# Adafruit_1_54in_eInk_Breakout.net
KiCad netlist of a schematic drawn in EAGLE
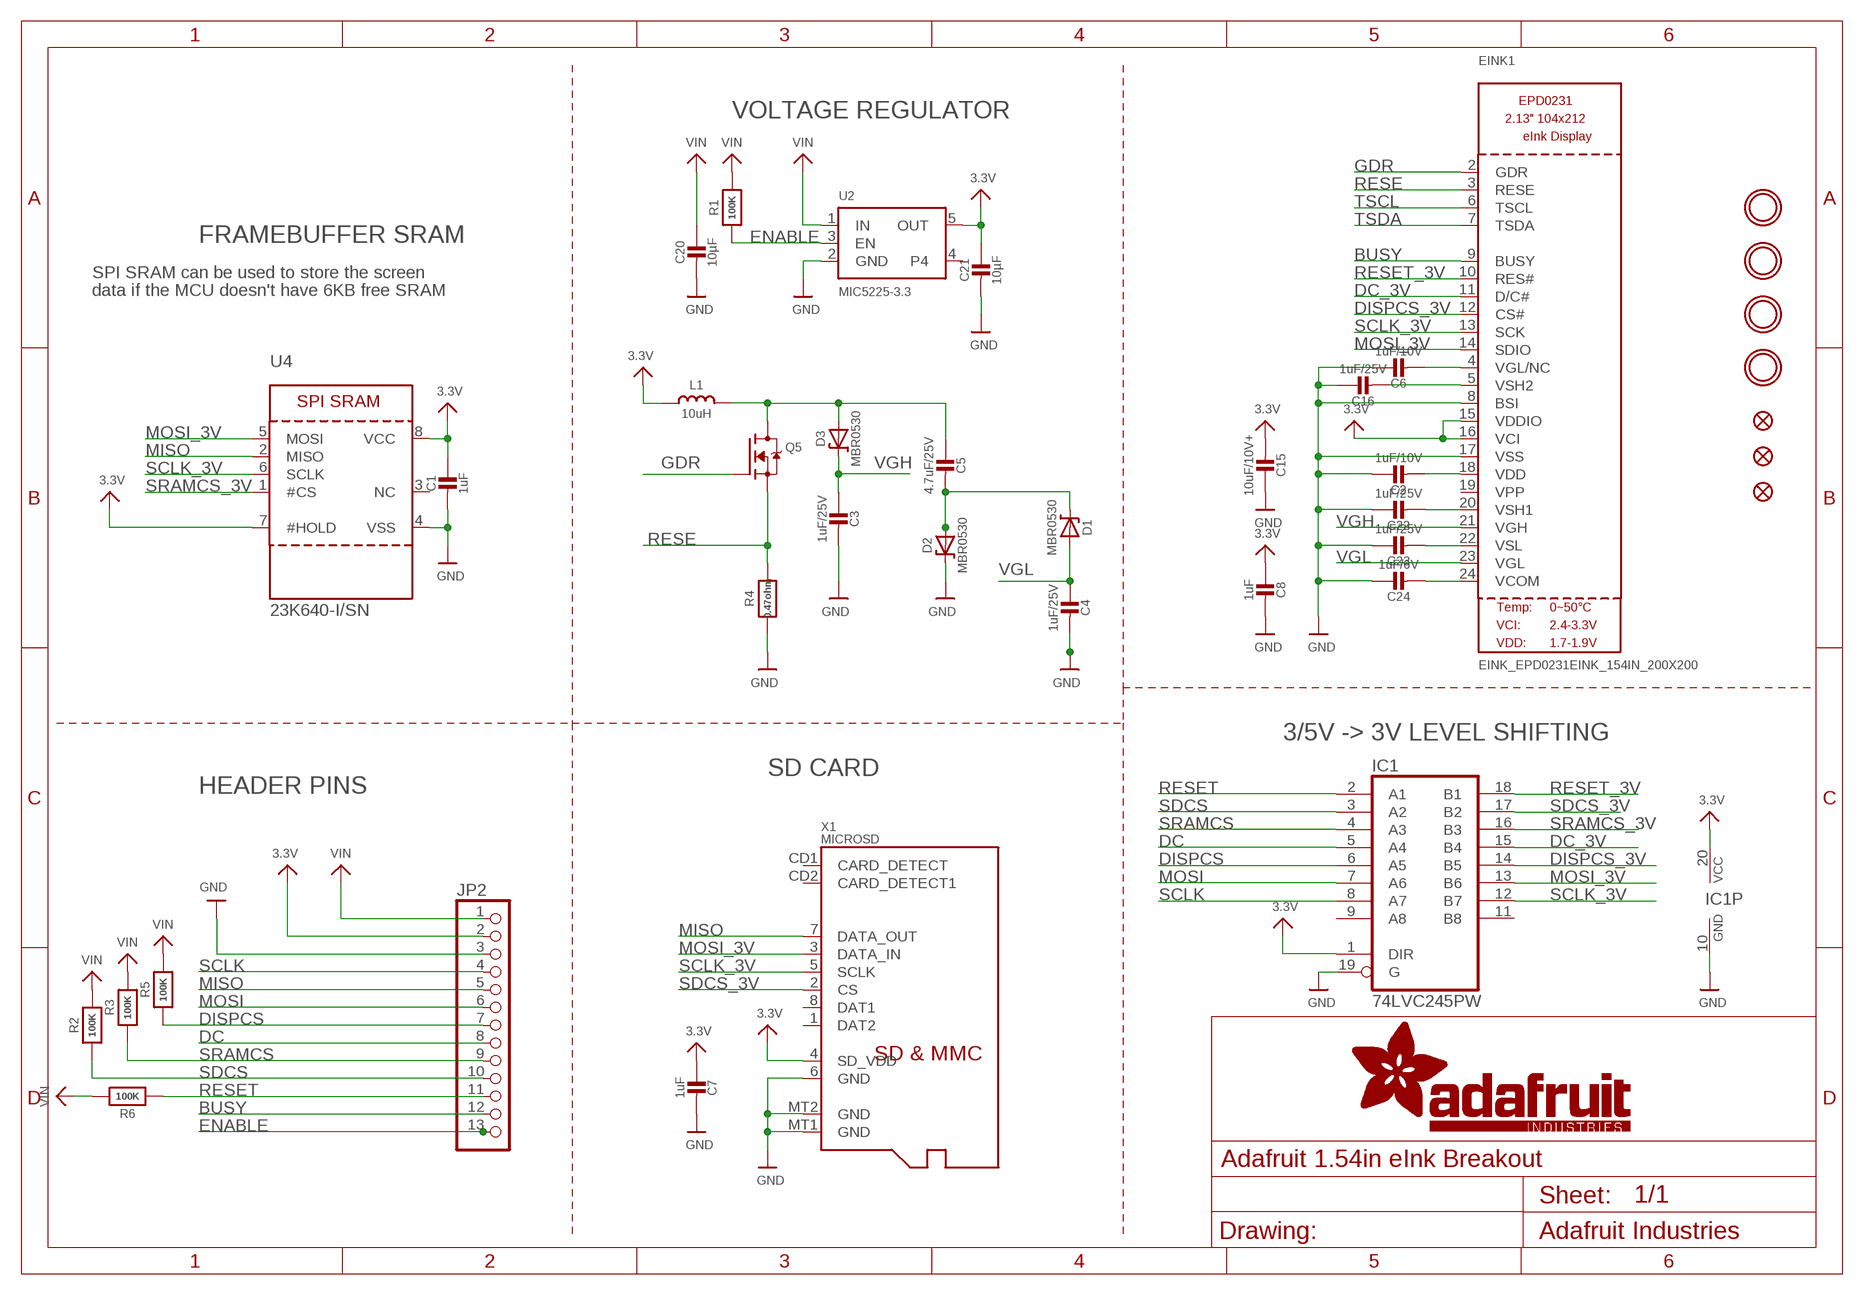
[diagram p0: schematic, sheet 1]

(export (version "E")
  (design (tool "Eeschema 10.0.6"))
  (components
    (comp (ref "C1")
      (value "1uF")
      (footprint "eagle-import:0805_10MGAP")
      (libsource (lib "eagle-import") (part "CAP_CERAMIC0805_10MGAP"))
    )
    (comp (ref "C2")
      (value "1uF/10V")
      (footprint "eagle-import:0805-NO")
      (libsource (lib "eagle-import") (part "CAP_CERAMIC0805-NOOUTLINE"))
    )
    (comp (ref "C3")
      (value "1uF/25V")
      (footprint "eagle-import:0805-NO")
      (libsource (lib "eagle-import") (part "CAP_CERAMIC0805-NOOUTLINE"))
    )
    (comp (ref "C4")
      (value "1uF/25V")
      (footprint "eagle-import:0805-NO")
      (libsource (lib "eagle-import") (part "CAP_CERAMIC0805-NOOUTLINE"))
    )
    (comp (ref "C5")
      (value "4.7uF/25V")
      (footprint "eagle-import:0805-NO")
      (libsource (lib "eagle-import") (part "CAP_CERAMIC0805-NOOUTLINE"))
    )
    (comp (ref "C6")
      (value "1uF/10V")
      (footprint "eagle-import:0805-NO")
      (libsource (lib "eagle-import") (part "CAP_CERAMIC0805-NOOUTLINE"))
    )
    (comp (ref "C7")
      (value "1uF")
      (footprint "eagle-import:0805-NO")
      (libsource (lib "eagle-import") (part "CAP_CERAMIC0805-NOOUTLINE"))
    )
    (comp (ref "C8")
      (value "1uF")
      (footprint "eagle-import:0805-NO")
      (libsource (lib "eagle-import") (part "CAP_CERAMIC0805-NOOUTLINE"))
    )
    (comp (ref "C15")
      (value "10uF/10V+")
      (footprint "eagle-import:0805-NO")
      (libsource (lib "eagle-import") (part "CAP_CERAMIC0805-NOOUTLINE"))
    )
    (comp (ref "C16")
      (value "1uF/25V")
      (footprint "eagle-import:0805-NO")
      (libsource (lib "eagle-import") (part "CAP_CERAMIC0805-NOOUTLINE"))
    )
    (comp (ref "C20")
      (value "10µF")
      (footprint "eagle-import:0805-NO")
      (libsource (lib "eagle-import") (part "CAP_CERAMIC0805-NOOUTLINE"))
    )
    (comp (ref "C21")
      (value "10µF")
      (footprint "eagle-import:0805-NO")
      (libsource (lib "eagle-import") (part "CAP_CERAMIC0805-NOOUTLINE"))
    )
    (comp (ref "C22")
      (value "1uF/25V")
      (footprint "eagle-import:0805-NO")
      (libsource (lib "eagle-import") (part "CAP_CERAMIC0805-NOOUTLINE"))
    )
    (comp (ref "C23")
      (value "1uF/25V")
      (footprint "eagle-import:0805-NO")
      (libsource (lib "eagle-import") (part "CAP_CERAMIC0805-NOOUTLINE"))
    )
    (comp (ref "C24")
      (value "1uF/6V")
      (footprint "eagle-import:0805-NO")
      (libsource (lib "eagle-import") (part "CAP_CERAMIC0805-NOOUTLINE"))
    )
    (comp (ref "D1")
      (value "MBR0530")
      (footprint "eagle-import:SOD-123")
      (libsource (lib "eagle-import") (part "DIODE-SCHOTTKYSOD-123"))
    )
    (comp (ref "D2")
      (value "MBR0530")
      (footprint "eagle-import:SOD-123")
      (libsource (lib "eagle-import") (part "DIODE-SCHOTTKYSOD-123"))
    )
    (comp (ref "D3")
      (value "MBR0530")
      (footprint "eagle-import:SOD-123")
      (libsource (lib "eagle-import") (part "DIODE-SCHOTTKYSOD-123"))
    )
    (comp (ref "EINK1")
      (value "EINK_EPD0231EINK_154IN_200X200")
      (footprint "eagle-import:EINK_154IN")
      (libsource (lib "eagle-import") (part "EINK_EPD0231EINK_154IN_200X200"))
    )
    (comp (ref "FID1")
      (value "FIDUCIAL_1MM")
      (footprint "eagle-import:FIDUCIAL_1MM")
      (libsource (lib "eagle-import") (part "FIDUCIAL_1MM"))
    )
    (comp (ref "FID2")
      (value "FIDUCIAL_1MM")
      (footprint "eagle-import:FIDUCIAL_1MM")
      (libsource (lib "eagle-import") (part "FIDUCIAL_1MM"))
    )
    (comp (ref "FID3")
      (value "FIDUCIAL_1MM")
      (footprint "eagle-import:FIDUCIAL_1MM")
      (libsource (lib "eagle-import") (part "FIDUCIAL_1MM"))
    )
    (comp (ref "IC1")
      (value "74LVC245PW")
      (footprint "eagle-import:TSSOP20")
      (libsource (lib "eagle-import") (part "74245TSSOP20"))
    )
    (comp (ref "JP2")
      (value "HEADER-1X13")
      (footprint "eagle-import:1X13_ROUND_70")
      (libsource (lib "eagle-import") (part "HEADER-1X13"))
    )
    (comp (ref "L1")
      (value "10uH")
      (footprint "eagle-import:INDUCTOR_4X4MM_NR401")
      (libsource (lib "eagle-import") (part "INDUCTORNR401"))
    )
    (comp (ref "Q5")
      (value "IRLML0100")
      (footprint "eagle-import:SOT23-3")
      (libsource (lib "eagle-import") (part "IRLML2060TRPBF"))
    )
    (comp (ref "R1")
      (value "100K")
      (footprint "eagle-import:0805-NO")
      (libsource (lib "eagle-import") (part "RESISTOR0805_NOOUTLINE"))
    )
    (comp (ref "R2")
      (value "100K")
      (footprint "eagle-import:0805-NO")
      (libsource (lib "eagle-import") (part "RESISTOR0805_NOOUTLINE"))
    )
    (comp (ref "R3")
      (value "100K")
      (footprint "eagle-import:0805-NO")
      (libsource (lib "eagle-import") (part "RESISTOR0805_NOOUTLINE"))
    )
    (comp (ref "R4")
      (value "0.47ohm")
      (footprint "eagle-import:0805_10MGAP")
      (libsource (lib "eagle-import") (part "RESISTOR0805_10MGAP"))
    )
    (comp (ref "R5")
      (value "100K")
      (footprint "eagle-import:0805-NO")
      (libsource (lib "eagle-import") (part "RESISTOR0805_NOOUTLINE"))
    )
    (comp (ref "R6")
      (value "100K")
      (footprint "eagle-import:0805-NO")
      (libsource (lib "eagle-import") (part "RESISTOR0805_NOOUTLINE"))
    )
    (comp (ref "U$3")
      (value "MOUNTINGHOLE2.5")
      (footprint "eagle-import:MOUNTINGHOLE_2.5_PLATED")
      (libsource (lib "eagle-import") (part "MOUNTINGHOLE2.5"))
    )
    (comp (ref "U$4")
      (value "MOUNTINGHOLE2.5")
      (footprint "eagle-import:MOUNTINGHOLE_2.5_PLATED")
      (libsource (lib "eagle-import") (part "MOUNTINGHOLE2.5"))
    )
    (comp (ref "U$5")
      (value "MOUNTINGHOLE2.5")
      (footprint "eagle-import:MOUNTINGHOLE_2.5_PLATED")
      (libsource (lib "eagle-import") (part "MOUNTINGHOLE2.5"))
    )
    (comp (ref "U$6")
      (value "MOUNTINGHOLE2.5")
      (footprint "eagle-import:MOUNTINGHOLE_2.5_PLATED")
      (libsource (lib "eagle-import") (part "MOUNTINGHOLE2.5"))
    )
    (comp (ref "U2")
      (value "MIC5225-3.3")
      (footprint "eagle-import:SOT23-5")
      (libsource (lib "eagle-import") (part "VREG_SOT23-5"))
    )
    (comp (ref "U4")
      (value "23K640-I/SN")
      (footprint "eagle-import:SOIC8_150MIL")
      (libsource (lib "eagle-import") (part "SRAM_SPI_SOIC8"))
    )
    (comp (ref "X1")
      (value "MICROSD")
      (footprint "eagle-import:MICROSD")
      (libsource (lib "eagle-import") (part "MICROSD"))
    )
  )
  (nets
    (net (code "1") (name "/BUSY") (class "Default")
      (node (ref "EINK1") (pin "9") (pinfunction "BUSY_9") (pintype "output"))
      (node (ref "JP2") (pin "12") (pinfunction "12_12") (pintype "passive"))
    )
    (net (code "2") (name "/DC") (class "Default")
      (node (ref "IC1") (pin "5") (pinfunction "A4_5") (pintype "bidirectional"))
      (node (ref "JP2") (pin "8") (pinfunction "8_8") (pintype "passive"))
    )
    (net (code "3") (name "/DC_3V") (class "Default")
      (node (ref "EINK1") (pin "11") (pinfunction "D/C#_11") (pintype "input"))
      (node (ref "IC1") (pin "15") (pinfunction "B4_15") (pintype "bidirectional"))
    )
    (net (code "4") (name "/DISPCS") (class "Default")
      (node (ref "IC1") (pin "6") (pinfunction "A5_6") (pintype "bidirectional"))
      (node (ref "JP2") (pin "7") (pinfunction "7_7") (pintype "passive"))
      (node (ref "R5") (pin "1") (pinfunction "1_1") (pintype "passive"))
    )
    (net (code "5") (name "/DISPCS_3V") (class "Default")
      (node (ref "EINK1") (pin "12") (pinfunction "CS#_12") (pintype "input"))
      (node (ref "IC1") (pin "14") (pinfunction "B5_14") (pintype "bidirectional"))
    )
    (net (code "6") (name "/ENABLE") (class "Default")
      (node (ref "JP2") (pin "13") (pinfunction "13_13") (pintype "passive"))
      (node (ref "R1") (pin "1") (pinfunction "1_1") (pintype "passive"))
      (node (ref "U2") (pin "3") (pinfunction "EN_3") (pintype "input"))
    )
    (net (code "7") (name "/GDR") (class "Default")
      (node (ref "EINK1") (pin "2") (pinfunction "GDR_2") (pintype "output"))
      (node (ref "Q5") (pin "1") (pinfunction "G_1") (pintype "bidirectional"))
    )
    (net (code "8") (name "/MISO") (class "Default")
      (node (ref "JP2") (pin "5") (pinfunction "5_5") (pintype "passive"))
      (node (ref "U4") (pin "2") (pinfunction "MISO_2") (pintype "output"))
      (node (ref "X1") (pin "7") (pinfunction "DATA_OUT_7") (pintype "output"))
    )
    (net (code "9") (name "/MOSI") (class "Default")
      (node (ref "IC1") (pin "7") (pinfunction "A6_7") (pintype "bidirectional"))
      (node (ref "JP2") (pin "6") (pinfunction "6_6") (pintype "passive"))
    )
    (net (code "10") (name "/MOSI_3V") (class "Default")
      (node (ref "EINK1") (pin "14") (pinfunction "SDIO_14") (pintype "bidirectional"))
      (node (ref "IC1") (pin "13") (pinfunction "B6_13") (pintype "bidirectional"))
      (node (ref "U4") (pin "5") (pinfunction "MOSI_5") (pintype "input"))
      (node (ref "X1") (pin "3") (pinfunction "DATA_IN_3") (pintype "input"))
    )
    (net (code "11") (name "/RESE") (class "Default")
      (node (ref "EINK1") (pin "3") (pinfunction "RESE_3") (pintype "input"))
      (node (ref "Q5") (pin "2") (pinfunction "S_2") (pintype "bidirectional"))
      (node (ref "R4") (pin "1") (pinfunction "1_1") (pintype "passive"))
    )
    (net (code "12") (name "/RESET") (class "Default")
      (node (ref "IC1") (pin "2") (pinfunction "A1_2") (pintype "bidirectional"))
      (node (ref "JP2") (pin "11") (pinfunction "11_11") (pintype "passive"))
      (node (ref "R6") (pin "1") (pinfunction "1_1") (pintype "passive"))
    )
    (net (code "13") (name "/RESET_3V") (class "Default")
      (node (ref "EINK1") (pin "10") (pinfunction "RES#_10") (pintype "input"))
      (node (ref "IC1") (pin "18") (pinfunction "B1_18") (pintype "bidirectional"))
    )
    (net (code "14") (name "/SCLK") (class "Default")
      (node (ref "IC1") (pin "8") (pinfunction "A7_8") (pintype "bidirectional"))
      (node (ref "JP2") (pin "4") (pinfunction "4_4") (pintype "passive"))
    )
    (net (code "15") (name "/SCLK_3V") (class "Default")
      (node (ref "EINK1") (pin "13") (pinfunction "SCK_13") (pintype "bidirectional"))
      (node (ref "IC1") (pin "12") (pinfunction "B7_12") (pintype "bidirectional"))
      (node (ref "U4") (pin "6") (pinfunction "SCLK_6") (pintype "input"))
      (node (ref "X1") (pin "5") (pinfunction "SCLK_5") (pintype "input"))
    )
    (net (code "16") (name "/SDCS") (class "Default")
      (node (ref "IC1") (pin "3") (pinfunction "A2_3") (pintype "bidirectional"))
      (node (ref "JP2") (pin "10") (pinfunction "10_10") (pintype "passive"))
      (node (ref "R2") (pin "1") (pinfunction "1_1") (pintype "passive"))
    )
    (net (code "17") (name "/SDCS_3V") (class "Default")
      (node (ref "IC1") (pin "17") (pinfunction "B2_17") (pintype "bidirectional"))
      (node (ref "X1") (pin "2") (pinfunction "CS_2") (pintype "input"))
    )
    (net (code "18") (name "/SRAMCS") (class "Default")
      (node (ref "IC1") (pin "4") (pinfunction "A3_4") (pintype "bidirectional"))
      (node (ref "JP2") (pin "9") (pinfunction "9_9") (pintype "passive"))
      (node (ref "R3") (pin "1") (pinfunction "1_1") (pintype "passive"))
    )
    (net (code "19") (name "/SRAMCS_3V") (class "Default")
      (node (ref "IC1") (pin "16") (pinfunction "B3_16") (pintype "bidirectional"))
      (node (ref "U4") (pin "1") (pinfunction "#CS_1") (pintype "input"))
    )
    (net (code "20") (name "/TSCL") (class "Default")
      (node (ref "EINK1") (pin "6") (pinfunction "TSCL_6") (pintype "output"))
    )
    (net (code "21") (name "/TSDA") (class "Default")
      (node (ref "EINK1") (pin "7") (pinfunction "TSDA_7") (pintype "bidirectional"))
    )
    (net (code "22") (name "/VGH") (class "Default")
      (node (ref "C3") (pin "1") (pinfunction "1_1") (pintype "passive"))
      (node (ref "D3") (pin "C") (pinfunction "C_C") (pintype "passive"))
      (node (ref "EINK1") (pin "21") (pinfunction "VGH_21") (pintype "passive"))
    )
    (net (code "23") (name "/VGL") (class "Default")
      (node (ref "C4") (pin "1") (pinfunction "1_1") (pintype "passive"))
      (node (ref "D1") (pin "A") (pinfunction "A_A") (pintype "passive"))
      (node (ref "EINK1") (pin "23") (pinfunction "VGL_23") (pintype "passive"))
    )
    (net (code "24") (name "3.3V") (class "Default")
      (node (ref "C1") (pin "1") (pinfunction "1_1") (pintype "passive"))
      (node (ref "C15") (pin "2") (pinfunction "2_2") (pintype "passive"))
      (node (ref "C21") (pin "1") (pinfunction "1_1") (pintype "passive"))
      (node (ref "C7") (pin "1") (pinfunction "1_1") (pintype "passive"))
      (node (ref "C8") (pin "1") (pinfunction "1_1") (pintype "passive"))
      (node (ref "EINK1") (pin "15") (pinfunction "VDDIO_15") (pintype "power_in"))
      (node (ref "EINK1") (pin "16") (pinfunction "VCI_16") (pintype "power_in"))
      (node (ref "IC1") (pin "1") (pinfunction "DIR_1") (pintype "input"))
      (node (ref "IC1") (pin "20") (pinfunction "VCC_20") (pintype "power_in"))
      (node (ref "JP2") (pin "2") (pinfunction "2_2") (pintype "passive"))
      (node (ref "L1") (pin "P$2") (pinfunction "2_P$2") (pintype "passive"))
      (node (ref "U2") (pin "5") (pinfunction "OUT_5") (pintype "power_in"))
      (node (ref "U4") (pin "7") (pinfunction "#HOLD_7") (pintype "input"))
      (node (ref "U4") (pin "8") (pinfunction "VCC_8") (pintype "power_in"))
      (node (ref "X1") (pin "4") (pinfunction "SD_VDD_4") (pintype "power_in"))
    )
    (net (code "25") (name "GND") (class "Default")
      (node (ref "C1") (pin "2") (pinfunction "2_2") (pintype "passive"))
      (node (ref "C15") (pin "1") (pinfunction "1_1") (pintype "passive"))
      (node (ref "C16") (pin "1") (pinfunction "1_1") (pintype "passive"))
      (node (ref "C2") (pin "1") (pinfunction "1_1") (pintype "passive"))
      (node (ref "C20") (pin "2") (pinfunction "2_2") (pintype "passive"))
      (node (ref "C21") (pin "2") (pinfunction "2_2") (pintype "passive"))
      (node (ref "C22") (pin "1") (pinfunction "1_1") (pintype "passive"))
      (node (ref "C23") (pin "1") (pinfunction "1_1") (pintype "passive"))
      (node (ref "C24") (pin "1") (pinfunction "1_1") (pintype "passive"))
      (node (ref "C3") (pin "2") (pinfunction "2_2") (pintype "passive"))
      (node (ref "C4") (pin "2") (pinfunction "2_2") (pintype "passive"))
      (node (ref "C6") (pin "1") (pinfunction "1_1") (pintype "passive"))
      (node (ref "C7") (pin "2") (pinfunction "2_2") (pintype "passive"))
      (node (ref "C8") (pin "2") (pinfunction "2_2") (pintype "passive"))
      (node (ref "D2") (pin "C") (pinfunction "C_C") (pintype "passive"))
      (node (ref "EINK1") (pin "17") (pinfunction "VSS_17") (pintype "power_in"))
      (node (ref "EINK1") (pin "8") (pinfunction "BSI_8") (pintype "input"))
      (node (ref "IC1") (pin "10") (pinfunction "GND_10") (pintype "power_in"))
      (node (ref "IC1") (pin "19") (pinfunction "G_19") (pintype "input"))
      (node (ref "JP2") (pin "3") (pinfunction "3_3") (pintype "passive"))
      (node (ref "R4") (pin "2") (pinfunction "2_2") (pintype "passive"))
      (node (ref "U2") (pin "2") (pinfunction "GND_2") (pintype "power_in"))
      (node (ref "U4") (pin "4") (pinfunction "VSS_4") (pintype "power_in"))
      (node (ref "X1") (pin "6") (pinfunction "GND_6") (pintype "power_in"))
      (node (ref "X1") (pin "MT1") (pinfunction "GND_MT1") (pintype "power_in"))
      (node (ref "X1") (pin "MT2") (pinfunction "GND_MT2") (pintype "power_in"))
    )
    (net (code "26") (name "Net-(C5-Pad2)") (class "Default")
      (node (ref "C5") (pin "2") (pinfunction "2_2") (pintype "passive"))
      (node (ref "D1") (pin "C") (pinfunction "C_C") (pintype "passive"))
      (node (ref "D2") (pin "A") (pinfunction "A_A") (pintype "passive"))
    )
    (net (code "27") (name "Net-(EINK1-VCOM)") (class "Default")
      (node (ref "C24") (pin "2") (pinfunction "2_2") (pintype "passive"))
      (node (ref "EINK1") (pin "24") (pinfunction "VCOM_24") (pintype "passive"))
    )
    (net (code "28") (name "Net-(EINK1-VDD)") (class "Default")
      (node (ref "C2") (pin "2") (pinfunction "2_2") (pintype "passive"))
      (node (ref "EINK1") (pin "18") (pinfunction "VDD_18") (pintype "passive"))
    )
    (net (code "29") (name "Net-(EINK1-VGL{slash}NC)") (class "Default")
      (node (ref "C6") (pin "2") (pinfunction "2_2") (pintype "passive"))
      (node (ref "EINK1") (pin "4") (pinfunction "VGL/NC_4") (pintype "bidirectional"))
    )
    (net (code "30") (name "Net-(EINK1-VSH1)") (class "Default")
      (node (ref "C22") (pin "2") (pinfunction "2_2") (pintype "passive"))
      (node (ref "EINK1") (pin "20") (pinfunction "VSH1_20") (pintype "passive"))
    )
    (net (code "31") (name "Net-(EINK1-VSH2)") (class "Default")
      (node (ref "C16") (pin "2") (pinfunction "2_2") (pintype "passive"))
      (node (ref "EINK1") (pin "5") (pinfunction "VSH2_5") (pintype "passive"))
    )
    (net (code "32") (name "Net-(EINK1-VSL)") (class "Default")
      (node (ref "C23") (pin "2") (pinfunction "2_2") (pintype "passive"))
      (node (ref "EINK1") (pin "22") (pinfunction "VSL_22") (pintype "passive"))
    )
    (net (code "33") (name "Net-(L1-1)") (class "Default")
      (node (ref "C5") (pin "1") (pinfunction "1_1") (pintype "passive"))
      (node (ref "D3") (pin "A") (pinfunction "A_A") (pintype "passive"))
      (node (ref "L1") (pin "P$1") (pinfunction "1_P$1") (pintype "passive"))
      (node (ref "Q5") (pin "3") (pinfunction "D_3") (pintype "bidirectional"))
    )
    (net (code "34") (name "VIN") (class "Default")
      (node (ref "C20") (pin "1") (pinfunction "1_1") (pintype "passive"))
      (node (ref "JP2") (pin "1") (pinfunction "1_1") (pintype "passive"))
      (node (ref "R1") (pin "2") (pinfunction "2_2") (pintype "passive"))
      (node (ref "R2") (pin "2") (pinfunction "2_2") (pintype "passive"))
      (node (ref "R3") (pin "2") (pinfunction "2_2") (pintype "passive"))
      (node (ref "R5") (pin "2") (pinfunction "2_2") (pintype "passive"))
      (node (ref "R6") (pin "2") (pinfunction "2_2") (pintype "passive"))
      (node (ref "U2") (pin "1") (pinfunction "IN_1") (pintype "power_in"))
    )
    (net (code "35") (name "unconnected-(EINK1-VPP-Pad19)") (class "Default")
      (node (ref "EINK1") (pin "19") (pinfunction "VPP_19") (pintype "passive"))
    )
    (net (code "36") (name "unconnected-(IC1A-A8-Pad9)") (class "Default")
      (node (ref "IC1") (pin "9") (pinfunction "A8_9") (pintype "bidirectional"))
    )
    (net (code "37") (name "unconnected-(IC1A-B8-Pad11)") (class "Default")
      (node (ref "IC1") (pin "11") (pinfunction "B8_11") (pintype "bidirectional"))
    )
    (net (code "38") (name "unconnected-(U2-P4-Pad4)") (class "Default")
      (node (ref "U2") (pin "4") (pinfunction "P4_4") (pintype "bidirectional"))
    )
    (net (code "39") (name "unconnected-(U4-NC-Pad3)") (class "Default")
      (node (ref "U4") (pin "3") (pinfunction "NC_3") (pintype "no_connect"))
    )
    (net (code "40") (name "unconnected-(X1-CARD_DETECT-PadCD1)") (class "Default")
      (node (ref "X1") (pin "CD1") (pinfunction "CARD_DETECT_CD1") (pintype "passive"))
    )
    (net (code "41") (name "unconnected-(X1-CARD_DETECT1-PadCD2)") (class "Default")
      (node (ref "X1") (pin "CD2") (pinfunction "CARD_DETECT1_CD2") (pintype "passive"))
    )
    (net (code "42") (name "unconnected-(X1-DAT1-Pad8)") (class "Default")
      (node (ref "X1") (pin "8") (pinfunction "DAT1_8") (pintype "bidirectional"))
    )
    (net (code "43") (name "unconnected-(X1-DAT2-Pad1)") (class "Default")
      (node (ref "X1") (pin "1") (pinfunction "DAT2_1") (pintype "bidirectional"))
    )
  )
)
